# Connectors.net
KiCad netlist of a schematic drawn in Altium Designer
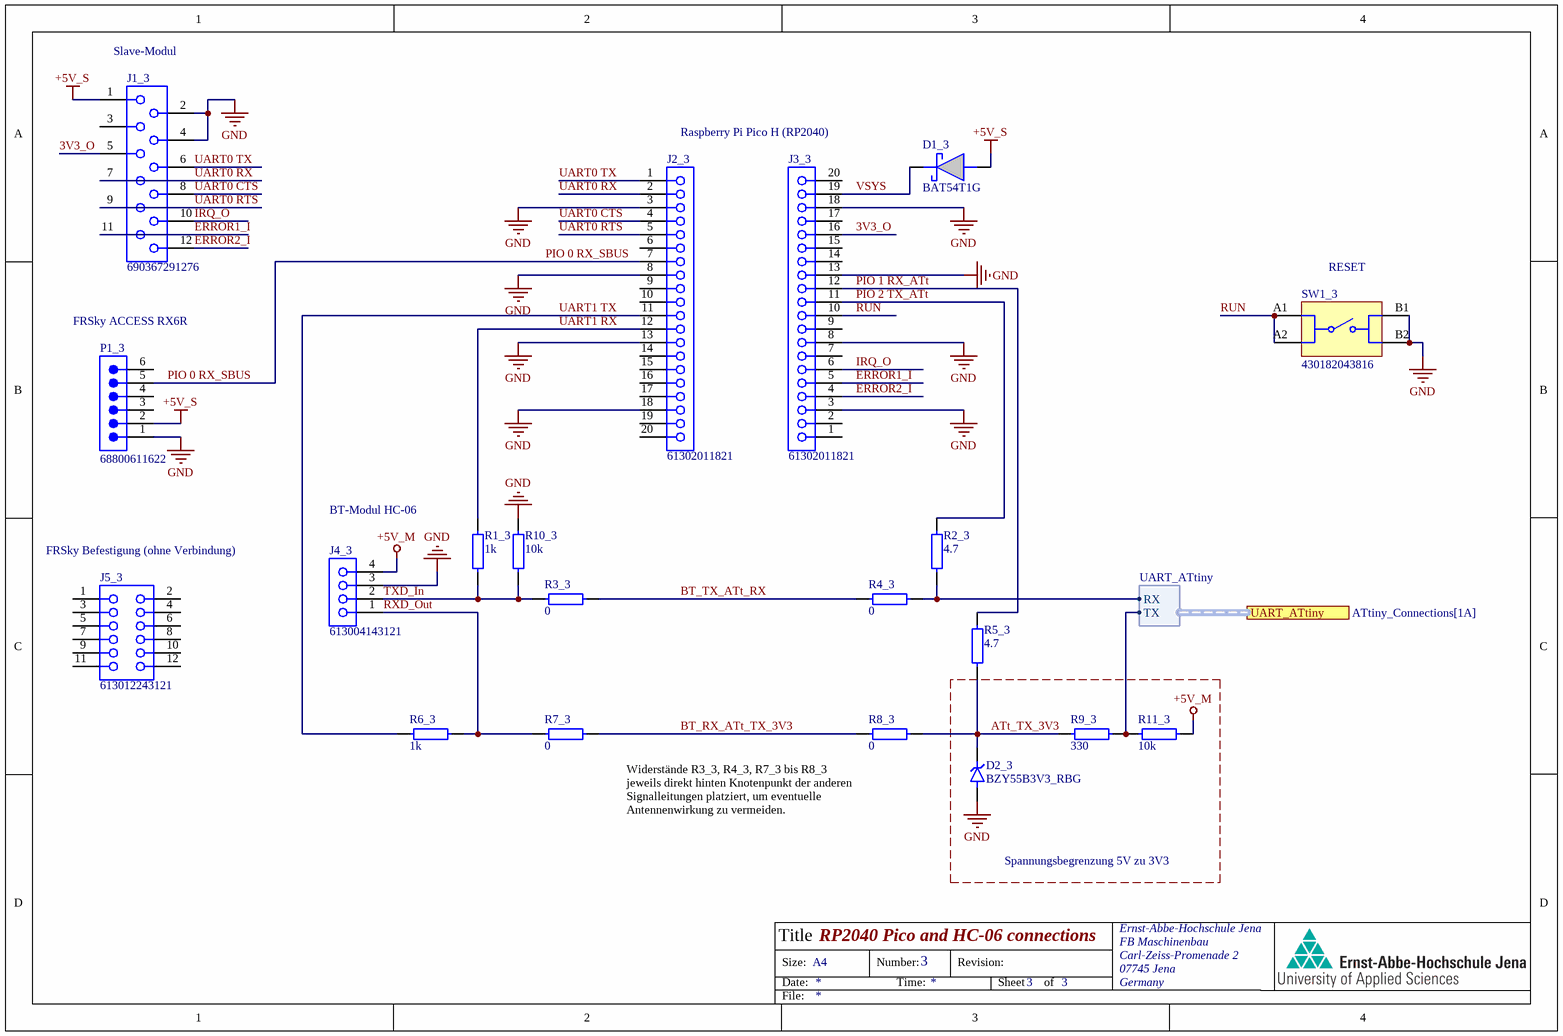
[diagram p0: Connectors.SchDoc]

(export (version "E")
  (design (tool "Eeschema 10.0.6"))
  (components
    (comp (ref "D1_3")
      (value "BAT54T1G")
      (footprint "SOD3716X135N")
      (fields (field (name "MOUSER PART NUMBER") "863-BAT54T1G"))
      (libsource (lib "BAT54T1G") (part "BAT54T1G"))
    )
    (comp (ref "D2_3")
      (value "BZY55B3V3_RBG")
      (footprint "DIO_BZY55B3V3_RBG")
      (libsource (lib "BZY55B3V3_RBG") (part "BZY55B3V3_RBG"))
    )
    (comp (ref "J1_3")
      (value "690367291276")
      (footprint "690367291276")
      (description "WR-MM Mini Module Connector, Female, SMT, with Latch & Polarization, Straight, pitch 2.54mm, 12p")
      (fields (field (name "MANUFACTURER") "Wurth Elektronik"))
      (libsource (lib "Altium_WR-MM (rev22a)") (part "690367291276"))
    )
    (comp (ref "J2_3")
      (value "61302011821")
      (footprint "61302011821")
      (description "WR-PHD Socket Header, THT, Vertical, pitch 2.54mm, 1 Row, 20P")
      (fields
        (field (name "MANUFACTURER PART NUMBER") "61302011821")
        (field (name "MANUFACTURER") "Wurth Elektronik")
      )
      (libsource (lib "Altium_WR-PHD (rev24a)") (part "61302011821"))
    )
    (comp (ref "J3_3")
      (value "61302011821")
      (footprint "61302011821")
      (description "WR-PHD Socket Header, THT, Vertical, pitch 2.54mm, 1 Row, 20P")
      (fields
        (field (name "MANUFACTURER PART NUMBER") "61302011821")
        (field (name "MANUFACTURER") "Wurth Elektronik")
      )
      (libsource (lib "Altium_WR-PHD (rev24a)") (part "61302011821"))
    )
    (comp (ref "J4_3")
      (value "613004143121")
      (footprint "613004143121")
      (description "WR-PHD Socket Header, THT, Angled, pitch 2.54mm, 1 Row, 4P")
      (fields
        (field (name "MANUFACTURER PART NUMBER") "613004143121")
        (field (name "MANUFACTURER") "Wurth Elektronik")
      )
      (libsource (lib "Altium_WR-PHD (rev24a)") (part "613004143121"))
    )
    (comp (ref "J5_3")
      (value "613012243121")
      (footprint "613012243121")
      (description "WR-PHD Socket Header, THT, Angled, pitch 2.54mm, 2 Row, 12P")
      (fields
        (field (name "MANUFACTURER PART NUMBER") "613012243121")
        (field (name "MANUFACTURER") "Wurth Elektronik")
      )
      (libsource (lib "Altium_WR-PHD (rev24a)") (part "613012243121"))
    )
    (comp (ref "P1_3")
      (value "68800611622")
      (footprint "68800611622")
      (description "WR-WTB “J” Type THT Vertical Male Shrouded Header, pitch 2.5 mm, 6 pins")
      (fields (field (name "MANUFACTURER") "Wurth Elektronik"))
      (libsource (lib "Altium_WR-WTB (rev25b)") (part "68800611622"))
    )
    (comp (ref "R1_3")
      (value "1k")
      (footprint "R-SMD-0805")
      (description "Widerstand")
      (libsource (lib "SMD") (part "R"))
    )
    (comp (ref "R2_3")
      (value "4.7")
      (footprint "R-SMD-0805")
      (description "Widerstand")
      (libsource (lib "SMD") (part "R"))
    )
    (comp (ref "R3_3")
      (value "0")
      (footprint "R-SMD-0805")
      (description "Widerstand")
      (libsource (lib "SMD") (part "R"))
    )
    (comp (ref "R4_3")
      (value "0")
      (footprint "R-SMD-0805")
      (description "Widerstand")
      (libsource (lib "SMD") (part "R"))
    )
    (comp (ref "R5_3")
      (value "4.7")
      (footprint "R-SMD-0805")
      (description "Widerstand")
      (libsource (lib "SMD") (part "R"))
    )
    (comp (ref "R6_3")
      (value "1k")
      (footprint "R-SMD-0805")
      (description "Widerstand")
      (libsource (lib "SMD") (part "R"))
    )
    (comp (ref "R7_3")
      (value "0")
      (footprint "R-SMD-0805")
      (description "Widerstand")
      (libsource (lib "SMD") (part "R"))
    )
    (comp (ref "R8_3")
      (value "0")
      (footprint "R-SMD-0805")
      (description "Widerstand")
      (libsource (lib "SMD") (part "R"))
    )
    (comp (ref "R9_3")
      (value "330")
      (footprint "R-SMD-0805")
      (description "Widerstand")
      (libsource (lib "SMD") (part "R"))
    )
    (comp (ref "R10_3")
      (value "10k")
      (footprint "R-SMD-0805")
      (description "Widerstand")
      (libsource (lib "SMD") (part "R"))
    )
    (comp (ref "R11_3")
      (value "10k")
      (footprint "R-SMD-0805")
      (description "Widerstand")
      (libsource (lib "SMD") (part "R"))
    )
    (comp (ref "SW1_3")
      (value "430182043816")
      (footprint "430182043816")
      (description "WS-TASV SMT Tact Switch, 6mm x 6mm, 160gf, SPST-NO, 12V, 50mA")
      (fields (field (name "MANUFACTURER") "Wurth Elektronik"))
      (libsource (lib "Altium_WS-TASV (rev24d)") (part "430182043816"))
    )
  )
  (nets
    (net (code "2") (name "+5V_M") (class "Default")
      (node (ref "J4_3") (pin "4") (pinfunction "4_4") (pintype "passive"))
      (node (ref "R11_3") (pin "1") (pinfunction "1_1") (pintype "passive"))
    )
    (net (code "3") (name "+5V_S") (class "Default")
      (node (ref "D1_3") (pin "2") (pinfunction "A_2") (pintype "passive"))
      (node (ref "J1_3") (pin "1") (pinfunction "1_1") (pintype "passive"))
      (node (ref "P1_3") (pin "2") (pinfunction "2_2") (pintype "passive"))
    )
    (net (code "4") (name "/3V3_O") (class "Default")
      (node (ref "J1_3") (pin "5") (pinfunction "5_5") (pintype "passive"))
      (node (ref "J3_3") (pin "16") (pinfunction "16_16") (pintype "passive"))
    )
    (net (code "5") (name "/ATt_TX_3V3") (class "Default")
      (node (ref "D2_3") (pin "C") (pinfunction "K_C") (pintype "passive"))
      (node (ref "R5_3") (pin "1") (pinfunction "1_1") (pintype "passive"))
      (node (ref "R8_3") (pin "2") (pinfunction "2_2") (pintype "passive"))
      (node (ref "R9_3") (pin "2") (pinfunction "2_2") (pintype "passive"))
    )
    (net (code "6") (name "/BT_RX_ATt_TX_3V3") (class "Default")
      (node (ref "R7_3") (pin "2") (pinfunction "2_2") (pintype "passive"))
      (node (ref "R8_3") (pin "1") (pinfunction "1_1") (pintype "passive"))
    )
    (net (code "7") (name "/BT_TX_ATt_RX") (class "Default")
      (node (ref "R3_3") (pin "2") (pinfunction "2_2") (pintype "passive"))
      (node (ref "R4_3") (pin "1") (pinfunction "1_1") (pintype "passive"))
    )
    (net (code "8") (name "/ERROR1_I") (class "Default")
      (node (ref "J1_3") (pin "11") (pinfunction "11_11") (pintype "passive"))
      (node (ref "J3_3") (pin "5") (pinfunction "5_5") (pintype "passive"))
    )
    (net (code "9") (name "/ERROR2_I") (class "Default")
      (node (ref "J1_3") (pin "12") (pinfunction "12_12") (pintype "passive"))
      (node (ref "J3_3") (pin "4") (pinfunction "4_4") (pintype "passive"))
    )
    (net (code "10") (name "/IRQ_O") (class "Default")
      (node (ref "J1_3") (pin "10") (pinfunction "10_10") (pintype "passive"))
      (node (ref "J3_3") (pin "6") (pinfunction "6_6") (pintype "passive"))
    )
    (net (code "11") (name "/PIO 0 RX_SBUS") (class "Default")
      (node (ref "J2_3") (pin "7") (pinfunction "7_7") (pintype "passive"))
      (node (ref "P1_3") (pin "5") (pinfunction "5_5") (pintype "passive"))
    )
    (net (code "12") (name "/PIO 1 RX_ATt") (class "Default")
      (node (ref "J3_3") (pin "12") (pinfunction "12_12") (pintype "passive"))
      (node (ref "R5_3") (pin "2") (pinfunction "2_2") (pintype "passive"))
    )
    (net (code "13") (name "/PIO 2 TX_ATt") (class "Default")
      (node (ref "J3_3") (pin "11") (pinfunction "11_11") (pintype "passive"))
      (node (ref "R2_3") (pin "2") (pinfunction "2_2") (pintype "passive"))
    )
    (net (code "14") (name "/RUN") (class "Default")
      (node (ref "J3_3") (pin "10") (pinfunction "10_10") (pintype "passive"))
      (node (ref "SW1_3") (pin "A1") (pinfunction "A1_A1") (pintype "passive"))
      (node (ref "SW1_3") (pin "A2") (pinfunction "A2_A2") (pintype "passive"))
    )
    (net (code "15") (name "/RXD_Out") (class "Default")
      (node (ref "J4_3") (pin "1") (pinfunction "1_1") (pintype "passive"))
      (node (ref "R6_3") (pin "2") (pinfunction "2_2") (pintype "passive"))
      (node (ref "R7_3") (pin "1") (pinfunction "1_1") (pintype "passive"))
    )
    (net (code "16") (name "/TXD_In") (class "Default")
      (node (ref "J4_3") (pin "2") (pinfunction "2_2") (pintype "passive"))
      (node (ref "R10_3") (pin "1") (pinfunction "1_1") (pintype "passive"))
      (node (ref "R1_3") (pin "1") (pinfunction "1_1") (pintype "passive"))
      (node (ref "R3_3") (pin "1") (pinfunction "1_1") (pintype "passive"))
    )
    (net (code "17") (name "/UART0 CTS") (class "Default")
      (node (ref "J1_3") (pin "8") (pinfunction "8_8") (pintype "passive"))
      (node (ref "J2_3") (pin "4") (pinfunction "4_4") (pintype "passive"))
    )
    (net (code "18") (name "/UART0 RTS") (class "Default")
      (node (ref "J1_3") (pin "9") (pinfunction "9_9") (pintype "passive"))
      (node (ref "J2_3") (pin "5") (pinfunction "5_5") (pintype "passive"))
    )
    (net (code "19") (name "/UART0 RX") (class "Default")
      (node (ref "J1_3") (pin "7") (pinfunction "7_7") (pintype "passive"))
      (node (ref "J2_3") (pin "2") (pinfunction "2_2") (pintype "passive"))
    )
    (net (code "20") (name "/UART0 TX") (class "Default")
      (node (ref "J1_3") (pin "6") (pinfunction "6_6") (pintype "passive"))
      (node (ref "J2_3") (pin "1") (pinfunction "1_1") (pintype "passive"))
    )
    (net (code "21") (name "/UART1 RX") (class "Default")
      (node (ref "J2_3") (pin "12") (pinfunction "12_12") (pintype "passive"))
      (node (ref "R1_3") (pin "2") (pinfunction "2_2") (pintype "passive"))
    )
    (net (code "22") (name "/UART1 TX") (class "Default")
      (node (ref "J2_3") (pin "11") (pinfunction "11_11") (pintype "passive"))
      (node (ref "R6_3") (pin "1") (pinfunction "1_1") (pintype "passive"))
    )
    (net (code "23") (name "/VSYS") (class "Default")
      (node (ref "D1_3") (pin "1") (pinfunction "K_1") (pintype "passive"))
      (node (ref "J3_3") (pin "19") (pinfunction "19_19") (pintype "passive"))
    )
    (net (code "25") (name "GND") (class "Default")
      (node (ref "D2_3") (pin "A") (pinfunction "A_A") (pintype "passive"))
      (node (ref "J1_3") (pin "2") (pinfunction "2_2") (pintype "passive"))
      (node (ref "J1_3") (pin "4") (pinfunction "4_4") (pintype "passive"))
      (node (ref "J2_3") (pin "13") (pinfunction "13_13") (pintype "passive"))
      (node (ref "J2_3") (pin "18") (pinfunction "18_18") (pintype "passive"))
      (node (ref "J2_3") (pin "3") (pinfunction "3_3") (pintype "passive"))
      (node (ref "J2_3") (pin "8") (pinfunction "8_8") (pintype "passive"))
      (node (ref "J3_3") (pin "13") (pinfunction "13_13") (pintype "passive"))
      (node (ref "J3_3") (pin "18") (pinfunction "18_18") (pintype "passive"))
      (node (ref "J3_3") (pin "3") (pinfunction "3_3") (pintype "passive"))
      (node (ref "J3_3") (pin "8") (pinfunction "8_8") (pintype "passive"))
      (node (ref "J4_3") (pin "3") (pinfunction "3_3") (pintype "passive"))
      (node (ref "P1_3") (pin "1") (pinfunction "1_1") (pintype "passive"))
      (node (ref "R10_3") (pin "2") (pinfunction "2_2") (pintype "passive"))
      (node (ref "SW1_3") (pin "B1") (pinfunction "B1_B1") (pintype "passive"))
      (node (ref "SW1_3") (pin "B2") (pinfunction "B2_B2") (pintype "passive"))
    )
    (net (code "26") (name "Net-(R2_3-Pad1)") (class "Default")
      (node (ref "R2_3") (pin "1") (pinfunction "1_1") (pintype "passive"))
      (node (ref "R4_3") (pin "2") (pinfunction "2_2") (pintype "passive"))
    )
    (net (code "27") (name "Net-(R11_3-Pad2)") (class "Default")
      (node (ref "R11_3") (pin "2") (pinfunction "2_2") (pintype "passive"))
      (node (ref "R9_3") (pin "1") (pinfunction "1_1") (pintype "passive"))
    )
    (net (code "28") (name "unconnected-(J1_3-Pad3)") (class "Default")
      (node (ref "J1_3") (pin "3") (pinfunction "3_3") (pintype "passive"))
    )
    (net (code "29") (name "unconnected-(J2_3-Pad6)") (class "Default")
      (node (ref "J2_3") (pin "6") (pinfunction "6_6") (pintype "passive"))
    )
    (net (code "30") (name "unconnected-(J2_3-Pad9)") (class "Default")
      (node (ref "J2_3") (pin "9") (pinfunction "9_9") (pintype "passive"))
    )
    (net (code "31") (name "unconnected-(J2_3-Pad10)") (class "Default")
      (node (ref "J2_3") (pin "10") (pinfunction "10_10") (pintype "passive"))
    )
    (net (code "32") (name "unconnected-(J2_3-Pad14)") (class "Default")
      (node (ref "J2_3") (pin "14") (pinfunction "14_14") (pintype "passive"))
    )
    (net (code "33") (name "unconnected-(J2_3-Pad15)") (class "Default")
      (node (ref "J2_3") (pin "15") (pinfunction "15_15") (pintype "passive"))
    )
    (net (code "34") (name "unconnected-(J2_3-Pad16)") (class "Default")
      (node (ref "J2_3") (pin "16") (pinfunction "16_16") (pintype "passive"))
    )
    (net (code "35") (name "unconnected-(J2_3-Pad17)") (class "Default")
      (node (ref "J2_3") (pin "17") (pinfunction "17_17") (pintype "passive"))
    )
    (net (code "36") (name "unconnected-(J2_3-Pad19)") (class "Default")
      (node (ref "J2_3") (pin "19") (pinfunction "19_19") (pintype "passive"))
    )
    (net (code "37") (name "unconnected-(J2_3-Pad20)") (class "Default")
      (node (ref "J2_3") (pin "20") (pinfunction "20_20") (pintype "passive"))
    )
    (net (code "38") (name "unconnected-(J3_3-Pad1)") (class "Default")
      (node (ref "J3_3") (pin "1") (pinfunction "1_1") (pintype "passive"))
    )
    (net (code "39") (name "unconnected-(J3_3-Pad2)") (class "Default")
      (node (ref "J3_3") (pin "2") (pinfunction "2_2") (pintype "passive"))
    )
    (net (code "40") (name "unconnected-(J3_3-Pad7)") (class "Default")
      (node (ref "J3_3") (pin "7") (pinfunction "7_7") (pintype "passive"))
    )
    (net (code "41") (name "unconnected-(J3_3-Pad9)") (class "Default")
      (node (ref "J3_3") (pin "9") (pinfunction "9_9") (pintype "passive"))
    )
    (net (code "42") (name "unconnected-(J3_3-Pad14)") (class "Default")
      (node (ref "J3_3") (pin "14") (pinfunction "14_14") (pintype "passive"))
    )
    (net (code "43") (name "unconnected-(J3_3-Pad15)") (class "Default")
      (node (ref "J3_3") (pin "15") (pinfunction "15_15") (pintype "passive"))
    )
    (net (code "44") (name "unconnected-(J3_3-Pad17)") (class "Default")
      (node (ref "J3_3") (pin "17") (pinfunction "17_17") (pintype "passive"))
    )
    (net (code "45") (name "unconnected-(J3_3-Pad20)") (class "Default")
      (node (ref "J3_3") (pin "20") (pinfunction "20_20") (pintype "passive"))
    )
    (net (code "46") (name "unconnected-(J5_3-Pad1)") (class "Default")
      (node (ref "J5_3") (pin "1") (pinfunction "1_1") (pintype "passive"))
    )
    (net (code "47") (name "unconnected-(J5_3-Pad2)") (class "Default")
      (node (ref "J5_3") (pin "2") (pinfunction "2_2") (pintype "passive"))
    )
    (net (code "48") (name "unconnected-(J5_3-Pad3)") (class "Default")
      (node (ref "J5_3") (pin "3") (pinfunction "3_3") (pintype "passive"))
    )
    (net (code "49") (name "unconnected-(J5_3-Pad4)") (class "Default")
      (node (ref "J5_3") (pin "4") (pinfunction "4_4") (pintype "passive"))
    )
    (net (code "50") (name "unconnected-(J5_3-Pad5)") (class "Default")
      (node (ref "J5_3") (pin "5") (pinfunction "5_5") (pintype "passive"))
    )
    (net (code "51") (name "unconnected-(J5_3-Pad6)") (class "Default")
      (node (ref "J5_3") (pin "6") (pinfunction "6_6") (pintype "passive"))
    )
    (net (code "52") (name "unconnected-(J5_3-Pad7)") (class "Default")
      (node (ref "J5_3") (pin "7") (pinfunction "7_7") (pintype "passive"))
    )
    (net (code "53") (name "unconnected-(J5_3-Pad8)") (class "Default")
      (node (ref "J5_3") (pin "8") (pinfunction "8_8") (pintype "passive"))
    )
    (net (code "54") (name "unconnected-(J5_3-Pad9)") (class "Default")
      (node (ref "J5_3") (pin "9") (pinfunction "9_9") (pintype "passive"))
    )
    (net (code "55") (name "unconnected-(J5_3-Pad10)") (class "Default")
      (node (ref "J5_3") (pin "10") (pinfunction "10_10") (pintype "passive"))
    )
    (net (code "56") (name "unconnected-(J5_3-Pad11)") (class "Default")
      (node (ref "J5_3") (pin "11") (pinfunction "11_11") (pintype "passive"))
    )
    (net (code "57") (name "unconnected-(J5_3-Pad12)") (class "Default")
      (node (ref "J5_3") (pin "12") (pinfunction "12_12") (pintype "passive"))
    )
    (net (code "58") (name "unconnected-(P1_3-Pad3)") (class "Default")
      (node (ref "P1_3") (pin "3") (pinfunction "3_3") (pintype "passive"))
    )
    (net (code "59") (name "unconnected-(P1_3-Pad4)") (class "Default")
      (node (ref "P1_3") (pin "4") (pinfunction "4_4") (pintype "passive"))
    )
    (net (code "60") (name "unconnected-(P1_3-Pad6)") (class "Default")
      (node (ref "P1_3") (pin "6") (pinfunction "6_6") (pintype "passive"))
    )
  )
)
